# Inputs.net
KiCad netlist of a schematic drawn in EAGLE
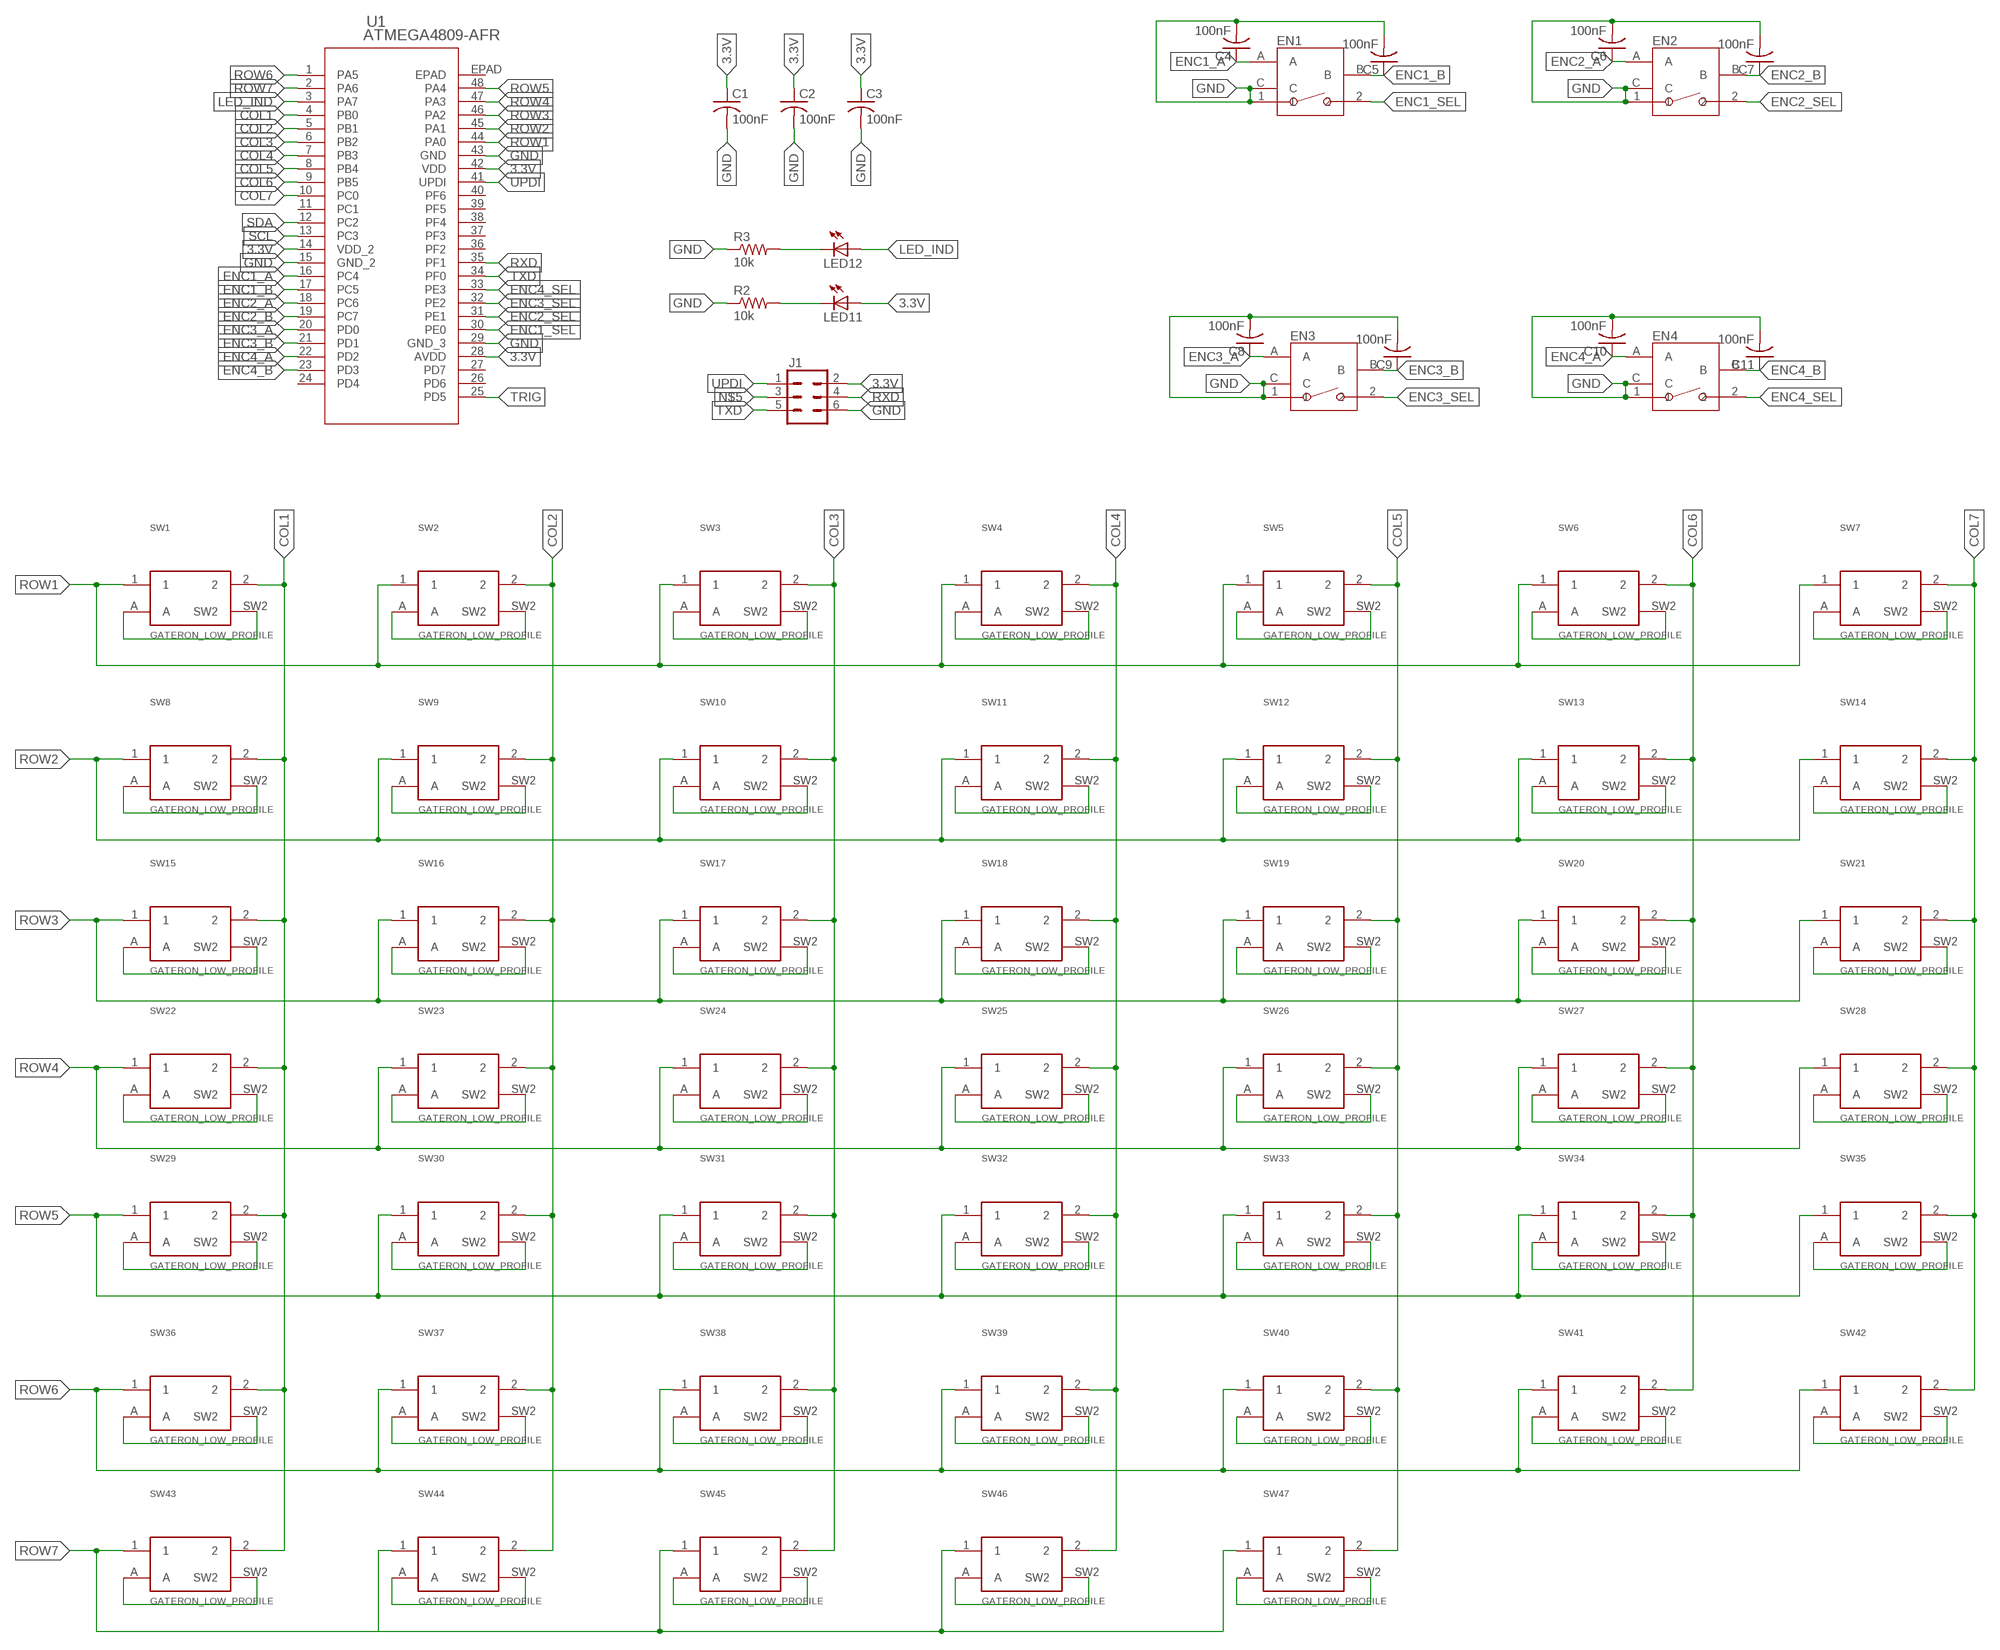
[diagram p0: schematic, sheet 1]

(export (version "E")
  (design (tool "Eeschema 10.0.6"))
  (components
    (comp (ref "C1")
      (value "100nF")
      (footprint "eagle-import:C0805")
      (libsource (lib "eagle-import") (part "C-USC0805"))
    )
    (comp (ref "C2")
      (value "100nF")
      (footprint "eagle-import:C0805")
      (libsource (lib "eagle-import") (part "C-USC0805"))
    )
    (comp (ref "C3")
      (value "100nF")
      (footprint "eagle-import:C0805")
      (libsource (lib "eagle-import") (part "C-USC0805"))
    )
    (comp (ref "C4")
      (value "100nF")
      (footprint "eagle-import:C0805")
      (libsource (lib "eagle-import") (part "C-USC0805"))
    )
    (comp (ref "C5")
      (value "100nF")
      (footprint "eagle-import:C0805")
      (libsource (lib "eagle-import") (part "C-USC0805"))
    )
    (comp (ref "C6")
      (value "100nF")
      (footprint "eagle-import:C0805")
      (libsource (lib "eagle-import") (part "C-USC0805"))
    )
    (comp (ref "C7")
      (value "100nF")
      (footprint "eagle-import:C0805")
      (libsource (lib "eagle-import") (part "C-USC0805"))
    )
    (comp (ref "C8")
      (value "100nF")
      (footprint "eagle-import:C0805")
      (libsource (lib "eagle-import") (part "C-USC0805"))
    )
    (comp (ref "C9")
      (value "100nF")
      (footprint "eagle-import:C0805")
      (libsource (lib "eagle-import") (part "C-USC0805"))
    )
    (comp (ref "C10")
      (value "100nF")
      (footprint "eagle-import:C0805")
      (libsource (lib "eagle-import") (part "C-USC0805"))
    )
    (comp (ref "C11")
      (value "100nF")
      (footprint "eagle-import:C0805")
      (libsource (lib "eagle-import") (part "C-USC0805"))
    )
    (comp (ref "EN1")
      (value "PEC11R-4215K-S0024")
      (footprint "eagle-import:PEC11R-4215K-S0024")
      (fields
        (field (name "DIGIKEY_PARTNO") "PEC11R-4215K-S0024-ND")
        (field (name "MANUFACTURER") "Bourns Inc.")
        (field (name "SPICEPREFIX") "X")
        (field (name "CREATED_BY") "PCBLayout.com")
      )
      (libsource (lib "eagle-import") (part "PEC11R-4215K-S0024"))
    )
    (comp (ref "EN2")
      (value "PEC11R-4215K-S0024")
      (footprint "eagle-import:PEC11R-4215K-S0024")
      (fields
        (field (name "DIGIKEY_PARTNO") "PEC11R-4215K-S0024-ND")
        (field (name "MANUFACTURER") "Bourns Inc.")
        (field (name "SPICEPREFIX") "X")
        (field (name "CREATED_BY") "PCBLayout.com")
      )
      (libsource (lib "eagle-import") (part "PEC11R-4215K-S0024"))
    )
    (comp (ref "EN3")
      (value "PEC11R-4215K-S0024")
      (footprint "eagle-import:PEC11R-4215K-S0024")
      (fields
        (field (name "DIGIKEY_PARTNO") "PEC11R-4215K-S0024-ND")
        (field (name "MANUFACTURER") "Bourns Inc.")
        (field (name "SPICEPREFIX") "X")
        (field (name "CREATED_BY") "PCBLayout.com")
      )
      (libsource (lib "eagle-import") (part "PEC11R-4215K-S0024"))
    )
    (comp (ref "EN4")
      (value "PEC11R-4215K-S0024")
      (footprint "eagle-import:PEC11R-4215K-S0024")
      (fields
        (field (name "DIGIKEY_PARTNO") "PEC11R-4215K-S0024-ND")
        (field (name "MANUFACTURER") "Bourns Inc.")
        (field (name "SPICEPREFIX") "X")
        (field (name "CREATED_BY") "PCBLayout.com")
      )
      (libsource (lib "eagle-import") (part "PEC11R-4215K-S0024"))
    )
    (comp (ref "J1")
      (value "CONN_03X2FEMALE_SMD")
      (footprint "eagle-import:2X3_SMD")
      (libsource (lib "eagle-import") (part "CONN_03X2FEMALE_SMD"))
    )
    (comp (ref "LED11")
      (value "LEDCHIPLED_0805")
      (footprint "eagle-import:CHIPLED_0805")
      (libsource (lib "eagle-import") (part "LEDCHIPLED_0805"))
    )
    (comp (ref "LED12")
      (value "LEDCHIPLED_0805")
      (footprint "eagle-import:CHIPLED_0805")
      (libsource (lib "eagle-import") (part "LEDCHIPLED_0805"))
    )
    (comp (ref "R2")
      (value "10k")
      (footprint "eagle-import:R0805")
      (libsource (lib "eagle-import") (part "R-US_R0805"))
    )
    (comp (ref "R3")
      (value "10k")
      (footprint "eagle-import:R0805")
      (libsource (lib "eagle-import") (part "R-US_R0805"))
    )
    (comp (ref "SW1")
      (value "GATERON_LOW_PROFILE")
      (footprint "eagle-import:GATERON_LP_PLAIN")
      (libsource (lib "eagle-import") (part "GATERON_LOW_PROFILE"))
    )
    (comp (ref "SW2")
      (value "GATERON_LOW_PROFILE")
      (footprint "eagle-import:GATERON_LP_PLAIN")
      (libsource (lib "eagle-import") (part "GATERON_LOW_PROFILE"))
    )
    (comp (ref "SW3")
      (value "GATERON_LOW_PROFILE")
      (footprint "eagle-import:GATERON_LP_PLAIN")
      (libsource (lib "eagle-import") (part "GATERON_LOW_PROFILE"))
    )
    (comp (ref "SW4")
      (value "GATERON_LOW_PROFILE")
      (footprint "eagle-import:GATERON_LP_PLAIN")
      (libsource (lib "eagle-import") (part "GATERON_LOW_PROFILE"))
    )
    (comp (ref "SW5")
      (value "GATERON_LOW_PROFILE")
      (footprint "eagle-import:GATERON_LP_PLAIN")
      (libsource (lib "eagle-import") (part "GATERON_LOW_PROFILE"))
    )
    (comp (ref "SW6")
      (value "GATERON_LOW_PROFILE")
      (footprint "eagle-import:GATERON_LP_PLAIN")
      (libsource (lib "eagle-import") (part "GATERON_LOW_PROFILE"))
    )
    (comp (ref "SW7")
      (value "GATERON_LOW_PROFILE")
      (footprint "eagle-import:GATERON_LP_PLAIN")
      (libsource (lib "eagle-import") (part "GATERON_LOW_PROFILE"))
    )
    (comp (ref "SW8")
      (value "GATERON_LOW_PROFILE")
      (footprint "eagle-import:GATERON_LP_PLAIN")
      (libsource (lib "eagle-import") (part "GATERON_LOW_PROFILE"))
    )
    (comp (ref "SW9")
      (value "GATERON_LOW_PROFILE")
      (footprint "eagle-import:GATERON_LP_PLAIN")
      (libsource (lib "eagle-import") (part "GATERON_LOW_PROFILE"))
    )
    (comp (ref "SW10")
      (value "GATERON_LOW_PROFILE")
      (footprint "eagle-import:GATERON_LP_PLAIN")
      (libsource (lib "eagle-import") (part "GATERON_LOW_PROFILE"))
    )
    (comp (ref "SW11")
      (value "GATERON_LOW_PROFILE")
      (footprint "eagle-import:GATERON_LP_PLAIN")
      (libsource (lib "eagle-import") (part "GATERON_LOW_PROFILE"))
    )
    (comp (ref "SW12")
      (value "GATERON_LOW_PROFILE")
      (footprint "eagle-import:GATERON_LP_PLAIN")
      (libsource (lib "eagle-import") (part "GATERON_LOW_PROFILE"))
    )
    (comp (ref "SW13")
      (value "GATERON_LOW_PROFILE")
      (footprint "eagle-import:GATERON_LP_PLAIN")
      (libsource (lib "eagle-import") (part "GATERON_LOW_PROFILE"))
    )
    (comp (ref "SW14")
      (value "GATERON_LOW_PROFILE")
      (footprint "eagle-import:GATERON_LP_PLAIN")
      (libsource (lib "eagle-import") (part "GATERON_LOW_PROFILE"))
    )
    (comp (ref "SW15")
      (value "GATERON_LOW_PROFILE")
      (footprint "eagle-import:GATERON_LP_PLAIN")
      (libsource (lib "eagle-import") (part "GATERON_LOW_PROFILE"))
    )
    (comp (ref "SW16")
      (value "GATERON_LOW_PROFILE")
      (footprint "eagle-import:GATERON_LP_PLAIN")
      (libsource (lib "eagle-import") (part "GATERON_LOW_PROFILE"))
    )
    (comp (ref "SW17")
      (value "GATERON_LOW_PROFILE")
      (footprint "eagle-import:GATERON_LP_PLAIN")
      (libsource (lib "eagle-import") (part "GATERON_LOW_PROFILE"))
    )
    (comp (ref "SW18")
      (value "GATERON_LOW_PROFILE")
      (footprint "eagle-import:GATERON_LP_PLAIN")
      (libsource (lib "eagle-import") (part "GATERON_LOW_PROFILE"))
    )
    (comp (ref "SW19")
      (value "GATERON_LOW_PROFILE")
      (footprint "eagle-import:GATERON_LP_PLAIN")
      (libsource (lib "eagle-import") (part "GATERON_LOW_PROFILE"))
    )
    (comp (ref "SW20")
      (value "GATERON_LOW_PROFILE")
      (footprint "eagle-import:GATERON_LP_PLAIN")
      (libsource (lib "eagle-import") (part "GATERON_LOW_PROFILE"))
    )
    (comp (ref "SW21")
      (value "GATERON_LOW_PROFILE")
      (footprint "eagle-import:GATERON_LP_PLAIN")
      (libsource (lib "eagle-import") (part "GATERON_LOW_PROFILE"))
    )
    (comp (ref "SW22")
      (value "GATERON_LOW_PROFILE")
      (footprint "eagle-import:GATERON_LP_PLAIN")
      (libsource (lib "eagle-import") (part "GATERON_LOW_PROFILE"))
    )
    (comp (ref "SW23")
      (value "GATERON_LOW_PROFILE")
      (footprint "eagle-import:GATERON_LP_PLAIN")
      (libsource (lib "eagle-import") (part "GATERON_LOW_PROFILE"))
    )
    (comp (ref "SW24")
      (value "GATERON_LOW_PROFILE")
      (footprint "eagle-import:GATERON_LP_PLAIN")
      (libsource (lib "eagle-import") (part "GATERON_LOW_PROFILE"))
    )
    (comp (ref "SW25")
      (value "GATERON_LOW_PROFILE")
      (footprint "eagle-import:GATERON_LP_PLAIN")
      (libsource (lib "eagle-import") (part "GATERON_LOW_PROFILE"))
    )
    (comp (ref "SW26")
      (value "GATERON_LOW_PROFILE")
      (footprint "eagle-import:GATERON_LP_PLAIN")
      (libsource (lib "eagle-import") (part "GATERON_LOW_PROFILE"))
    )
    (comp (ref "SW27")
      (value "GATERON_LOW_PROFILE")
      (footprint "eagle-import:GATERON_LP_PLAIN")
      (libsource (lib "eagle-import") (part "GATERON_LOW_PROFILE"))
    )
    (comp (ref "SW28")
      (value "GATERON_LOW_PROFILE")
      (footprint "eagle-import:GATERON_LP_PLAIN")
      (libsource (lib "eagle-import") (part "GATERON_LOW_PROFILE"))
    )
    (comp (ref "SW29")
      (value "GATERON_LOW_PROFILE")
      (footprint "eagle-import:GATERON_LP_PLAIN")
      (libsource (lib "eagle-import") (part "GATERON_LOW_PROFILE"))
    )
    (comp (ref "SW30")
      (value "GATERON_LOW_PROFILE")
      (footprint "eagle-import:GATERON_LP_PLAIN")
      (libsource (lib "eagle-import") (part "GATERON_LOW_PROFILE"))
    )
    (comp (ref "SW31")
      (value "GATERON_LOW_PROFILE")
      (footprint "eagle-import:GATERON_LP_PLAIN")
      (libsource (lib "eagle-import") (part "GATERON_LOW_PROFILE"))
    )
    (comp (ref "SW32")
      (value "GATERON_LOW_PROFILE")
      (footprint "eagle-import:GATERON_LP_PLAIN")
      (libsource (lib "eagle-import") (part "GATERON_LOW_PROFILE"))
    )
    (comp (ref "SW33")
      (value "GATERON_LOW_PROFILE")
      (footprint "eagle-import:GATERON_LP_PLAIN")
      (libsource (lib "eagle-import") (part "GATERON_LOW_PROFILE"))
    )
    (comp (ref "SW34")
      (value "GATERON_LOW_PROFILE")
      (footprint "eagle-import:GATERON_LP_PLAIN")
      (libsource (lib "eagle-import") (part "GATERON_LOW_PROFILE"))
    )
    (comp (ref "SW35")
      (value "GATERON_LOW_PROFILE")
      (footprint "eagle-import:GATERON_LP_PLAIN")
      (libsource (lib "eagle-import") (part "GATERON_LOW_PROFILE"))
    )
    (comp (ref "SW36")
      (value "GATERON_LOW_PROFILE")
      (footprint "eagle-import:GATERON_LP_PLAIN")
      (libsource (lib "eagle-import") (part "GATERON_LOW_PROFILE"))
    )
    (comp (ref "SW37")
      (value "GATERON_LOW_PROFILE")
      (footprint "eagle-import:GATERON_LP_PLAIN")
      (libsource (lib "eagle-import") (part "GATERON_LOW_PROFILE"))
    )
    (comp (ref "SW38")
      (value "GATERON_LOW_PROFILE")
      (footprint "eagle-import:GATERON_LP_PLAIN")
      (libsource (lib "eagle-import") (part "GATERON_LOW_PROFILE"))
    )
    (comp (ref "SW39")
      (value "GATERON_LOW_PROFILE")
      (footprint "eagle-import:GATERON_LP_PLAIN")
      (libsource (lib "eagle-import") (part "GATERON_LOW_PROFILE"))
    )
    (comp (ref "SW40")
      (value "GATERON_LOW_PROFILE")
      (footprint "eagle-import:GATERON_LP_PLAIN")
      (libsource (lib "eagle-import") (part "GATERON_LOW_PROFILE"))
    )
    (comp (ref "SW41")
      (value "GATERON_LOW_PROFILE")
      (footprint "eagle-import:GATERON_LP_PLAIN")
      (libsource (lib "eagle-import") (part "GATERON_LOW_PROFILE"))
    )
    (comp (ref "SW42")
      (value "GATERON_LOW_PROFILE")
      (footprint "eagle-import:GATERON_LP_PLAIN")
      (libsource (lib "eagle-import") (part "GATERON_LOW_PROFILE"))
    )
    (comp (ref "SW43")
      (value "GATERON_LOW_PROFILE")
      (footprint "eagle-import:GATERON_LP_PLAIN")
      (libsource (lib "eagle-import") (part "GATERON_LOW_PROFILE"))
    )
    (comp (ref "SW44")
      (value "GATERON_LOW_PROFILE")
      (footprint "eagle-import:GATERON_LP_PLAIN")
      (libsource (lib "eagle-import") (part "GATERON_LOW_PROFILE"))
    )
    (comp (ref "SW45")
      (value "GATERON_LOW_PROFILE")
      (footprint "eagle-import:GATERON_LP_PLAIN")
      (libsource (lib "eagle-import") (part "GATERON_LOW_PROFILE"))
    )
    (comp (ref "SW46")
      (value "GATERON_LOW_PROFILE")
      (footprint "eagle-import:GATERON_LP_PLAIN")
      (libsource (lib "eagle-import") (part "GATERON_LOW_PROFILE"))
    )
    (comp (ref "SW47")
      (value "GATERON_LOW_PROFILE")
      (footprint "eagle-import:GATERON_LP_PLAIN")
      (libsource (lib "eagle-import") (part "GATERON_LOW_PROFILE"))
    )
    (comp (ref "U1")
      (value "ATMEGA4809-AFR")
      (footprint "eagle-import:TQFP48_7X7MC_MCH")
      (fields (field (name "COPYRIGHT") "Copyright (C) 2018 Accelerated Designs. All rights reserved"))
      (libsource (lib "eagle-import") (part "ATMEGA4809-AFR"))
    )
  )
  (nets
    (net (code "1") (name "3.3V") (class "Default")
      (node (ref "C1") (pin "1") (pinfunction "1_1") (pintype "passive"))
      (node (ref "C2") (pin "1") (pinfunction "1_1") (pintype "passive"))
      (node (ref "C3") (pin "1") (pinfunction "1_1") (pintype "passive"))
      (node (ref "J1") (pin "2") (pinfunction "2_2") (pintype "bidirectional"))
      (node (ref "LED11") (pin "A") (pinfunction "A_A") (pintype "passive"))
      (node (ref "U1") (pin "14") (pinfunction "VDD_2_14") (pintype "power_in"))
      (node (ref "U1") (pin "28") (pinfunction "AVDD_28") (pintype "power_in"))
      (node (ref "U1") (pin "42") (pinfunction "VDD_42") (pintype "power_in"))
    )
    (net (code "2") (name "COL1") (class "Default")
      (node (ref "SW1") (pin "2") (pinfunction "2_2") (pintype "bidirectional"))
      (node (ref "SW15") (pin "2") (pinfunction "2_2") (pintype "bidirectional"))
      (node (ref "SW22") (pin "2") (pinfunction "2_2") (pintype "bidirectional"))
      (node (ref "SW29") (pin "2") (pinfunction "2_2") (pintype "bidirectional"))
      (node (ref "SW36") (pin "2") (pinfunction "2_2") (pintype "bidirectional"))
      (node (ref "SW43") (pin "2") (pinfunction "2_2") (pintype "bidirectional"))
      (node (ref "SW8") (pin "2") (pinfunction "2_2") (pintype "bidirectional"))
      (node (ref "U1") (pin "4") (pinfunction "PB0_4") (pintype "bidirectional"))
    )
    (net (code "3") (name "COL2") (class "Default")
      (node (ref "SW16") (pin "2") (pinfunction "2_2") (pintype "bidirectional"))
      (node (ref "SW2") (pin "2") (pinfunction "2_2") (pintype "bidirectional"))
      (node (ref "SW23") (pin "2") (pinfunction "2_2") (pintype "bidirectional"))
      (node (ref "SW30") (pin "2") (pinfunction "2_2") (pintype "bidirectional"))
      (node (ref "SW37") (pin "2") (pinfunction "2_2") (pintype "bidirectional"))
      (node (ref "SW44") (pin "2") (pinfunction "2_2") (pintype "bidirectional"))
      (node (ref "SW9") (pin "2") (pinfunction "2_2") (pintype "bidirectional"))
      (node (ref "U1") (pin "5") (pinfunction "PB1_5") (pintype "bidirectional"))
    )
    (net (code "4") (name "COL3") (class "Default")
      (node (ref "SW10") (pin "2") (pinfunction "2_2") (pintype "bidirectional"))
      (node (ref "SW17") (pin "2") (pinfunction "2_2") (pintype "bidirectional"))
      (node (ref "SW24") (pin "2") (pinfunction "2_2") (pintype "bidirectional"))
      (node (ref "SW3") (pin "2") (pinfunction "2_2") (pintype "bidirectional"))
      (node (ref "SW31") (pin "2") (pinfunction "2_2") (pintype "bidirectional"))
      (node (ref "SW38") (pin "2") (pinfunction "2_2") (pintype "bidirectional"))
      (node (ref "SW45") (pin "2") (pinfunction "2_2") (pintype "bidirectional"))
      (node (ref "U1") (pin "6") (pinfunction "PB2_6") (pintype "bidirectional"))
    )
    (net (code "5") (name "COL4") (class "Default")
      (node (ref "SW11") (pin "2") (pinfunction "2_2") (pintype "bidirectional"))
      (node (ref "SW18") (pin "2") (pinfunction "2_2") (pintype "bidirectional"))
      (node (ref "SW25") (pin "2") (pinfunction "2_2") (pintype "bidirectional"))
      (node (ref "SW32") (pin "2") (pinfunction "2_2") (pintype "bidirectional"))
      (node (ref "SW39") (pin "2") (pinfunction "2_2") (pintype "bidirectional"))
      (node (ref "SW4") (pin "2") (pinfunction "2_2") (pintype "bidirectional"))
      (node (ref "SW46") (pin "2") (pinfunction "2_2") (pintype "bidirectional"))
      (node (ref "U1") (pin "7") (pinfunction "PB3_7") (pintype "bidirectional"))
    )
    (net (code "6") (name "COL5") (class "Default")
      (node (ref "SW12") (pin "2") (pinfunction "2_2") (pintype "bidirectional"))
      (node (ref "SW19") (pin "2") (pinfunction "2_2") (pintype "bidirectional"))
      (node (ref "SW26") (pin "2") (pinfunction "2_2") (pintype "bidirectional"))
      (node (ref "SW33") (pin "2") (pinfunction "2_2") (pintype "bidirectional"))
      (node (ref "SW40") (pin "2") (pinfunction "2_2") (pintype "bidirectional"))
      (node (ref "SW47") (pin "2") (pinfunction "2_2") (pintype "bidirectional"))
      (node (ref "SW5") (pin "2") (pinfunction "2_2") (pintype "bidirectional"))
      (node (ref "U1") (pin "8") (pinfunction "PB4_8") (pintype "bidirectional"))
    )
    (net (code "7") (name "COL6") (class "Default")
      (node (ref "SW13") (pin "2") (pinfunction "2_2") (pintype "bidirectional"))
      (node (ref "SW20") (pin "2") (pinfunction "2_2") (pintype "bidirectional"))
      (node (ref "SW27") (pin "2") (pinfunction "2_2") (pintype "bidirectional"))
      (node (ref "SW34") (pin "2") (pinfunction "2_2") (pintype "bidirectional"))
      (node (ref "SW41") (pin "2") (pinfunction "2_2") (pintype "bidirectional"))
      (node (ref "SW6") (pin "2") (pinfunction "2_2") (pintype "bidirectional"))
      (node (ref "U1") (pin "9") (pinfunction "PB5_9") (pintype "bidirectional"))
    )
    (net (code "8") (name "COL7") (class "Default")
      (node (ref "SW14") (pin "2") (pinfunction "2_2") (pintype "bidirectional"))
      (node (ref "SW21") (pin "2") (pinfunction "2_2") (pintype "bidirectional"))
      (node (ref "SW28") (pin "2") (pinfunction "2_2") (pintype "bidirectional"))
      (node (ref "SW35") (pin "2") (pinfunction "2_2") (pintype "bidirectional"))
      (node (ref "SW42") (pin "2") (pinfunction "2_2") (pintype "bidirectional"))
      (node (ref "SW7") (pin "2") (pinfunction "2_2") (pintype "bidirectional"))
      (node (ref "U1") (pin "10") (pinfunction "PC0_10") (pintype "bidirectional"))
    )
    (net (code "9") (name "ENC1_A") (class "Default")
      (node (ref "C4") (pin "1") (pinfunction "1_1") (pintype "passive"))
      (node (ref "EN1") (pin "A") (pinfunction "A_A") (pintype "passive"))
      (node (ref "U1") (pin "16") (pinfunction "PC4_16") (pintype "bidirectional"))
    )
    (net (code "10") (name "ENC1_B") (class "Default")
      (node (ref "C5") (pin "1") (pinfunction "1_1") (pintype "passive"))
      (node (ref "EN1") (pin "B") (pinfunction "B_B") (pintype "passive"))
      (node (ref "U1") (pin "17") (pinfunction "PC5_17") (pintype "bidirectional"))
    )
    (net (code "11") (name "ENC1_SEL") (class "Default")
      (node (ref "EN1") (pin "2") (pinfunction "2_2") (pintype "passive"))
      (node (ref "U1") (pin "30") (pinfunction "PE0_30") (pintype "bidirectional"))
    )
    (net (code "12") (name "ENC2_A") (class "Default")
      (node (ref "C6") (pin "1") (pinfunction "1_1") (pintype "passive"))
      (node (ref "EN2") (pin "A") (pinfunction "A_A") (pintype "passive"))
      (node (ref "U1") (pin "18") (pinfunction "PC6_18") (pintype "bidirectional"))
    )
    (net (code "13") (name "ENC2_B") (class "Default")
      (node (ref "C7") (pin "1") (pinfunction "1_1") (pintype "passive"))
      (node (ref "EN2") (pin "B") (pinfunction "B_B") (pintype "passive"))
      (node (ref "U1") (pin "19") (pinfunction "PC7_19") (pintype "bidirectional"))
    )
    (net (code "14") (name "ENC2_SEL") (class "Default")
      (node (ref "EN2") (pin "2") (pinfunction "2_2") (pintype "passive"))
      (node (ref "U1") (pin "31") (pinfunction "PE1_31") (pintype "bidirectional"))
    )
    (net (code "15") (name "ENC3_A") (class "Default")
      (node (ref "C8") (pin "1") (pinfunction "1_1") (pintype "passive"))
      (node (ref "EN3") (pin "A") (pinfunction "A_A") (pintype "passive"))
      (node (ref "U1") (pin "20") (pinfunction "PD0_20") (pintype "bidirectional"))
    )
    (net (code "16") (name "ENC3_B") (class "Default")
      (node (ref "C9") (pin "1") (pinfunction "1_1") (pintype "passive"))
      (node (ref "EN3") (pin "B") (pinfunction "B_B") (pintype "passive"))
      (node (ref "U1") (pin "21") (pinfunction "PD1_21") (pintype "bidirectional"))
    )
    (net (code "17") (name "ENC3_SEL") (class "Default")
      (node (ref "EN3") (pin "2") (pinfunction "2_2") (pintype "passive"))
      (node (ref "U1") (pin "32") (pinfunction "PE2_32") (pintype "bidirectional"))
    )
    (net (code "18") (name "ENC4_A") (class "Default")
      (node (ref "C10") (pin "1") (pinfunction "1_1") (pintype "passive"))
      (node (ref "EN4") (pin "A") (pinfunction "A_A") (pintype "passive"))
      (node (ref "U1") (pin "22") (pinfunction "PD2_22") (pintype "bidirectional"))
    )
    (net (code "19") (name "ENC4_B") (class "Default")
      (node (ref "C11") (pin "1") (pinfunction "1_1") (pintype "passive"))
      (node (ref "EN4") (pin "B") (pinfunction "B_B") (pintype "passive"))
      (node (ref "U1") (pin "23") (pinfunction "PD3_23") (pintype "bidirectional"))
    )
    (net (code "20") (name "ENC4_SEL") (class "Default")
      (node (ref "EN4") (pin "2") (pinfunction "2_2") (pintype "passive"))
      (node (ref "U1") (pin "33") (pinfunction "PE3_33") (pintype "bidirectional"))
    )
    (net (code "21") (name "GND") (class "Default")
      (node (ref "C1") (pin "2") (pinfunction "2_2") (pintype "passive"))
      (node (ref "C10") (pin "2") (pinfunction "2_2") (pintype "passive"))
      (node (ref "C11") (pin "2") (pinfunction "2_2") (pintype "passive"))
      (node (ref "C2") (pin "2") (pinfunction "2_2") (pintype "passive"))
      (node (ref "C3") (pin "2") (pinfunction "2_2") (pintype "passive"))
      (node (ref "C4") (pin "2") (pinfunction "2_2") (pintype "passive"))
      (node (ref "C5") (pin "2") (pinfunction "2_2") (pintype "passive"))
      (node (ref "C6") (pin "2") (pinfunction "2_2") (pintype "passive"))
      (node (ref "C7") (pin "2") (pinfunction "2_2") (pintype "passive"))
      (node (ref "C8") (pin "2") (pinfunction "2_2") (pintype "passive"))
      (node (ref "C9") (pin "2") (pinfunction "2_2") (pintype "passive"))
      (node (ref "EN1") (pin "1") (pinfunction "1_1") (pintype "passive"))
      (node (ref "EN1") (pin "C") (pinfunction "C_C") (pintype "passive"))
      (node (ref "EN2") (pin "1") (pinfunction "1_1") (pintype "passive"))
      (node (ref "EN2") (pin "C") (pinfunction "C_C") (pintype "passive"))
      (node (ref "EN3") (pin "1") (pinfunction "1_1") (pintype "passive"))
      (node (ref "EN3") (pin "C") (pinfunction "C_C") (pintype "passive"))
      (node (ref "EN4") (pin "1") (pinfunction "1_1") (pintype "passive"))
      (node (ref "EN4") (pin "C") (pinfunction "C_C") (pintype "passive"))
      (node (ref "J1") (pin "6") (pinfunction "6_6") (pintype "bidirectional"))
      (node (ref "R2") (pin "1") (pinfunction "1_1") (pintype "passive"))
      (node (ref "R3") (pin "1") (pinfunction "1_1") (pintype "passive"))
      (node (ref "U1") (pin "15") (pinfunction "GND_2_15") (pintype "power_in"))
      (node (ref "U1") (pin "29") (pinfunction "GND_3_29") (pintype "power_in"))
      (node (ref "U1") (pin "43") (pinfunction "GND_43") (pintype "power_in"))
    )
    (net (code "22") (name "LED_IND") (class "Default")
      (node (ref "LED12") (pin "A") (pinfunction "A_A") (pintype "passive"))
      (node (ref "U1") (pin "3") (pinfunction "PA7_3") (pintype "bidirectional"))
    )
    (net (code "23") (name "N$5") (class "Default")
      (node (ref "J1") (pin "3") (pinfunction "3_3") (pintype "bidirectional"))
    )
    (net (code "24") (name "Net-(LED11-PadC)") (class "Default")
      (node (ref "LED11") (pin "C") (pinfunction "C_C") (pintype "passive"))
      (node (ref "R2") (pin "2") (pinfunction "2_2") (pintype "passive"))
    )
    (net (code "25") (name "Net-(LED12-PadC)") (class "Default")
      (node (ref "LED12") (pin "C") (pinfunction "C_C") (pintype "passive"))
      (node (ref "R3") (pin "2") (pinfunction "2_2") (pintype "passive"))
    )
    (net (code "26") (name "Net-(SW1-PadA)") (class "Default")
      (node (ref "SW1") (pin "A") (pinfunction "A_A") (pintype "bidirectional"))
      (node (ref "SW1") (pin "SW2") (pinfunction "SW2_SW2") (pintype "bidirectional"))
    )
    (net (code "27") (name "Net-(SW2-PadA)") (class "Default")
      (node (ref "SW2") (pin "A") (pinfunction "A_A") (pintype "bidirectional"))
      (node (ref "SW2") (pin "SW2") (pinfunction "SW2_SW2") (pintype "bidirectional"))
    )
    (net (code "28") (name "Net-(SW3-PadA)") (class "Default")
      (node (ref "SW3") (pin "A") (pinfunction "A_A") (pintype "bidirectional"))
      (node (ref "SW3") (pin "SW2") (pinfunction "SW2_SW2") (pintype "bidirectional"))
    )
    (net (code "29") (name "Net-(SW4-PadA)") (class "Default")
      (node (ref "SW4") (pin "A") (pinfunction "A_A") (pintype "bidirectional"))
      (node (ref "SW4") (pin "SW2") (pinfunction "SW2_SW2") (pintype "bidirectional"))
    )
    (net (code "30") (name "Net-(SW5-PadA)") (class "Default")
      (node (ref "SW5") (pin "A") (pinfunction "A_A") (pintype "bidirectional"))
      (node (ref "SW5") (pin "SW2") (pinfunction "SW2_SW2") (pintype "bidirectional"))
    )
    (net (code "31") (name "Net-(SW6-PadA)") (class "Default")
      (node (ref "SW6") (pin "A") (pinfunction "A_A") (pintype "bidirectional"))
      (node (ref "SW6") (pin "SW2") (pinfunction "SW2_SW2") (pintype "bidirectional"))
    )
    (net (code "32") (name "Net-(SW7-PadA)") (class "Default")
      (node (ref "SW7") (pin "A") (pinfunction "A_A") (pintype "bidirectional"))
      (node (ref "SW7") (pin "SW2") (pinfunction "SW2_SW2") (pintype "bidirectional"))
    )
    (net (code "33") (name "Net-(SW8-PadA)") (class "Default")
      (node (ref "SW8") (pin "A") (pinfunction "A_A") (pintype "bidirectional"))
      (node (ref "SW8") (pin "SW2") (pinfunction "SW2_SW2") (pintype "bidirectional"))
    )
    (net (code "34") (name "Net-(SW9-PadA)") (class "Default")
      (node (ref "SW9") (pin "A") (pinfunction "A_A") (pintype "bidirectional"))
      (node (ref "SW9") (pin "SW2") (pinfunction "SW2_SW2") (pintype "bidirectional"))
    )
    (net (code "35") (name "Net-(SW10-PadA)") (class "Default")
      (node (ref "SW10") (pin "A") (pinfunction "A_A") (pintype "bidirectional"))
      (node (ref "SW10") (pin "SW2") (pinfunction "SW2_SW2") (pintype "bidirectional"))
    )
    (net (code "36") (name "Net-(SW11-PadA)") (class "Default")
      (node (ref "SW11") (pin "A") (pinfunction "A_A") (pintype "bidirectional"))
      (node (ref "SW11") (pin "SW2") (pinfunction "SW2_SW2") (pintype "bidirectional"))
    )
    (net (code "37") (name "Net-(SW12-PadA)") (class "Default")
      (node (ref "SW12") (pin "A") (pinfunction "A_A") (pintype "bidirectional"))
      (node (ref "SW12") (pin "SW2") (pinfunction "SW2_SW2") (pintype "bidirectional"))
    )
    (net (code "38") (name "Net-(SW13-PadA)") (class "Default")
      (node (ref "SW13") (pin "A") (pinfunction "A_A") (pintype "bidirectional"))
      (node (ref "SW13") (pin "SW2") (pinfunction "SW2_SW2") (pintype "bidirectional"))
    )
    (net (code "39") (name "Net-(SW14-PadA)") (class "Default")
      (node (ref "SW14") (pin "A") (pinfunction "A_A") (pintype "bidirectional"))
      (node (ref "SW14") (pin "SW2") (pinfunction "SW2_SW2") (pintype "bidirectional"))
    )
    (net (code "40") (name "Net-(SW15-PadA)") (class "Default")
      (node (ref "SW15") (pin "A") (pinfunction "A_A") (pintype "bidirectional"))
      (node (ref "SW15") (pin "SW2") (pinfunction "SW2_SW2") (pintype "bidirectional"))
    )
    (net (code "41") (name "Net-(SW16-PadA)") (class "Default")
      (node (ref "SW16") (pin "A") (pinfunction "A_A") (pintype "bidirectional"))
      (node (ref "SW16") (pin "SW2") (pinfunction "SW2_SW2") (pintype "bidirectional"))
    )
    (net (code "42") (name "Net-(SW17-PadA)") (class "Default")
      (node (ref "SW17") (pin "A") (pinfunction "A_A") (pintype "bidirectional"))
      (node (ref "SW17") (pin "SW2") (pinfunction "SW2_SW2") (pintype "bidirectional"))
    )
    (net (code "43") (name "Net-(SW18-PadA)") (class "Default")
      (node (ref "SW18") (pin "A") (pinfunction "A_A") (pintype "bidirectional"))
      (node (ref "SW18") (pin "SW2") (pinfunction "SW2_SW2") (pintype "bidirectional"))
    )
    (net (code "44") (name "Net-(SW19-PadA)") (class "Default")
      (node (ref "SW19") (pin "A") (pinfunction "A_A") (pintype "bidirectional"))
      (node (ref "SW19") (pin "SW2") (pinfunction "SW2_SW2") (pintype "bidirectional"))
    )
    (net (code "45") (name "Net-(SW20-PadA)") (class "Default")
      (node (ref "SW20") (pin "A") (pinfunction "A_A") (pintype "bidirectional"))
      (node (ref "SW20") (pin "SW2") (pinfunction "SW2_SW2") (pintype "bidirectional"))
    )
    (net (code "46") (name "Net-(SW21-PadA)") (class "Default")
      (node (ref "SW21") (pin "A") (pinfunction "A_A") (pintype "bidirectional"))
      (node (ref "SW21") (pin "SW2") (pinfunction "SW2_SW2") (pintype "bidirectional"))
    )
    (net (code "47") (name "Net-(SW22-PadA)") (class "Default")
      (node (ref "SW22") (pin "A") (pinfunction "A_A") (pintype "bidirectional"))
      (node (ref "SW22") (pin "SW2") (pinfunction "SW2_SW2") (pintype "bidirectional"))
    )
    (net (code "48") (name "Net-(SW23-PadA)") (class "Default")
      (node (ref "SW23") (pin "A") (pinfunction "A_A") (pintype "bidirectional"))
      (node (ref "SW23") (pin "SW2") (pinfunction "SW2_SW2") (pintype "bidirectional"))
    )
    (net (code "49") (name "Net-(SW24-PadA)") (class "Default")
      (node (ref "SW24") (pin "A") (pinfunction "A_A") (pintype "bidirectional"))
      (node (ref "SW24") (pin "SW2") (pinfunction "SW2_SW2") (pintype "bidirectional"))
    )
    (net (code "50") (name "Net-(SW25-PadA)") (class "Default")
      (node (ref "SW25") (pin "A") (pinfunction "A_A") (pintype "bidirectional"))
      (node (ref "SW25") (pin "SW2") (pinfunction "SW2_SW2") (pintype "bidirectional"))
    )
    (net (code "51") (name "Net-(SW26-PadA)") (class "Default")
      (node (ref "SW26") (pin "A") (pinfunction "A_A") (pintype "bidirectional"))
      (node (ref "SW26") (pin "SW2") (pinfunction "SW2_SW2") (pintype "bidirectional"))
    )
    (net (code "52") (name "Net-(SW27-PadA)") (class "Default")
      (node (ref "SW27") (pin "A") (pinfunction "A_A") (pintype "bidirectional"))
      (node (ref "SW27") (pin "SW2") (pinfunction "SW2_SW2") (pintype "bidirectional"))
    )
    (net (code "53") (name "Net-(SW28-PadA)") (class "Default")
      (node (ref "SW28") (pin "A") (pinfunction "A_A") (pintype "bidirectional"))
      (node (ref "SW28") (pin "SW2") (pinfunction "SW2_SW2") (pintype "bidirectional"))
    )
    (net (code "54") (name "Net-(SW29-PadA)") (class "Default")
      (node (ref "SW29") (pin "A") (pinfunction "A_A") (pintype "bidirectional"))
      (node (ref "SW29") (pin "SW2") (pinfunction "SW2_SW2") (pintype "bidirectional"))
    )
    (net (code "55") (name "Net-(SW30-PadA)") (class "Default")
      (node (ref "SW30") (pin "A") (pinfunction "A_A") (pintype "bidirectional"))
      (node (ref "SW30") (pin "SW2") (pinfunction "SW2_SW2") (pintype "bidirectional"))
    )
    (net (code "56") (name "Net-(SW31-PadA)") (class "Default")
      (node (ref "SW31") (pin "A") (pinfunction "A_A") (pintype "bidirectional"))
      (node (ref "SW31") (pin "SW2") (pinfunction "SW2_SW2") (pintype "bidirectional"))
    )
    (net (code "57") (name "Net-(SW32-PadA)") (class "Default")
      (node (ref "SW32") (pin "A") (pinfunction "A_A") (pintype "bidirectional"))
      (node (ref "SW32") (pin "SW2") (pinfunction "SW2_SW2") (pintype "bidirectional"))
    )
    (net (code "58") (name "Net-(SW33-PadA)") (class "Default")
      (node (ref "SW33") (pin "A") (pinfunction "A_A") (pintype "bidirectional"))
      (node (ref "SW33") (pin "SW2") (pinfunction "SW2_SW2") (pintype "bidirectional"))
    )
    (net (code "59") (name "Net-(SW34-PadA)") (class "Default")
      (node (ref "SW34") (pin "A") (pinfunction "A_A") (pintype "bidirectional"))
      (node (ref "SW34") (pin "SW2") (pinfunction "SW2_SW2") (pintype "bidirectional"))
    )
    (net (code "60") (name "Net-(SW35-PadA)") (class "Default")
      (node (ref "SW35") (pin "A") (pinfunction "A_A") (pintype "bidirectional"))
      (node (ref "SW35") (pin "SW2") (pinfunction "SW2_SW2") (pintype "bidirectional"))
    )
    (net (code "61") (name "Net-(SW36-PadA)") (class "Default")
      (node (ref "SW36") (pin "A") (pinfunction "A_A") (pintype "bidirectional"))
      (node (ref "SW36") (pin "SW2") (pinfunction "SW2_SW2") (pintype "bidirectional"))
    )
    (net (code "62") (name "Net-(SW37-PadA)") (class "Default")
      (node (ref "SW37") (pin "A") (pinfunction "A_A") (pintype "bidirectional"))
      (node (ref "SW37") (pin "SW2") (pinfunction "SW2_SW2") (pintype "bidirectional"))
    )
    (net (code "63") (name "Net-(SW38-PadA)") (class "Default")
      (node (ref "SW38") (pin "A") (pinfunction "A_A") (pintype "bidirectional"))
      (node (ref "SW38") (pin "SW2") (pinfunction "SW2_SW2") (pintype "bidirectional"))
    )
    (net (code "64") (name "Net-(SW39-PadA)") (class "Default")
      (node (ref "SW39") (pin "A") (pinfunction "A_A") (pintype "bidirectional"))
      (node (ref "SW39") (pin "SW2") (pinfunction "SW2_SW2") (pintype "bidirectional"))
    )
    (net (code "65") (name "Net-(SW40-PadA)") (class "Default")
      (node (ref "SW40") (pin "A") (pinfunction "A_A") (pintype "bidirectional"))
      (node (ref "SW40") (pin "SW2") (pinfunction "SW2_SW2") (pintype "bidirectional"))
    )
    (net (code "66") (name "Net-(SW41-PadA)") (class "Default")
      (node (ref "SW41") (pin "A") (pinfunction "A_A") (pintype "bidirectional"))
      (node (ref "SW41") (pin "SW2") (pinfunction "SW2_SW2") (pintype "bidirectional"))
    )
    (net (code "67") (name "Net-(SW42-PadA)") (class "Default")
      (node (ref "SW42") (pin "A") (pinfunction "A_A") (pintype "bidirectional"))
      (node (ref "SW42") (pin "SW2") (pinfunction "SW2_SW2") (pintype "bidirectional"))
    )
    (net (code "68") (name "Net-(SW43-PadA)") (class "Default")
      (node (ref "SW43") (pin "A") (pinfunction "A_A") (pintype "bidirectional"))
      (node (ref "SW43") (pin "SW2") (pinfunction "SW2_SW2") (pintype "bidirectional"))
    )
    (net (code "69") (name "Net-(SW44-PadA)") (class "Default")
      (node (ref "SW44") (pin "A") (pinfunction "A_A") (pintype "bidirectional"))
      (node (ref "SW44") (pin "SW2") (pinfunction "SW2_SW2") (pintype "bidirectional"))
    )
    (net (code "70") (name "Net-(SW45-PadA)") (class "Default")
      (node (ref "SW45") (pin "A") (pinfunction "A_A") (pintype "bidirectional"))
      (node (ref "SW45") (pin "SW2") (pinfunction "SW2_SW2") (pintype "bidirectional"))
    )
    (net (code "71") (name "Net-(SW46-PadA)") (class "Default")
      (node (ref "SW46") (pin "A") (pinfunction "A_A") (pintype "bidirectional"))
      (node (ref "SW46") (pin "SW2") (pinfunction "SW2_SW2") (pintype "bidirectional"))
    )
    (net (code "72") (name "Net-(SW47-PadA)") (class "Default")
      (node (ref "SW47") (pin "A") (pinfunction "A_A") (pintype "bidirectional"))
      (node (ref "SW47") (pin "SW2") (pinfunction "SW2_SW2") (pintype "bidirectional"))
    )
    (net (code "73") (name "ROW1") (class "Default")
      (node (ref "SW1") (pin "1") (pinfunction "1_1") (pintype "bidirectional"))
      (node (ref "SW2") (pin "1") (pinfunction "1_1") (pintype "bidirectional"))
      (node (ref "SW3") (pin "1") (pinfunction "1_1") (pintype "bidirectional"))
      (node (ref "SW4") (pin "1") (pinfunction "1_1") (pintype "bidirectional"))
      (node (ref "SW5") (pin "1") (pinfunction "1_1") (pintype "bidirectional"))
      (node (ref "SW6") (pin "1") (pinfunction "1_1") (pintype "bidirectional"))
      (node (ref "SW7") (pin "1") (pinfunction "1_1") (pintype "bidirectional"))
      (node (ref "U1") (pin "44") (pinfunction "PA0_44") (pintype "bidirectional"))
    )
    (net (code "74") (name "ROW2") (class "Default")
      (node (ref "SW10") (pin "1") (pinfunction "1_1") (pintype "bidirectional"))
      (node (ref "SW11") (pin "1") (pinfunction "1_1") (pintype "bidirectional"))
      (node (ref "SW12") (pin "1") (pinfunction "1_1") (pintype "bidirectional"))
      (node (ref "SW13") (pin "1") (pinfunction "1_1") (pintype "bidirectional"))
      (node (ref "SW14") (pin "1") (pinfunction "1_1") (pintype "bidirectional"))
      (node (ref "SW8") (pin "1") (pinfunction "1_1") (pintype "bidirectional"))
      (node (ref "SW9") (pin "1") (pinfunction "1_1") (pintype "bidirectional"))
      (node (ref "U1") (pin "45") (pinfunction "PA1_45") (pintype "bidirectional"))
    )
    (net (code "75") (name "ROW3") (class "Default")
      (node (ref "SW15") (pin "1") (pinfunction "1_1") (pintype "bidirectional"))
      (node (ref "SW16") (pin "1") (pinfunction "1_1") (pintype "bidirectional"))
      (node (ref "SW17") (pin "1") (pinfunction "1_1") (pintype "bidirectional"))
      (node (ref "SW18") (pin "1") (pinfunction "1_1") (pintype "bidirectional"))
      (node (ref "SW19") (pin "1") (pinfunction "1_1") (pintype "bidirectional"))
      (node (ref "SW20") (pin "1") (pinfunction "1_1") (pintype "bidirectional"))
      (node (ref "SW21") (pin "1") (pinfunction "1_1") (pintype "bidirectional"))
      (node (ref "U1") (pin "46") (pinfunction "PA2_46") (pintype "bidirectional"))
    )
    (net (code "76") (name "ROW4") (class "Default")
      (node (ref "SW22") (pin "1") (pinfunction "1_1") (pintype "bidirectional"))
      (node (ref "SW23") (pin "1") (pinfunction "1_1") (pintype "bidirectional"))
      (node (ref "SW24") (pin "1") (pinfunction "1_1") (pintype "bidirectional"))
      (node (ref "SW25") (pin "1") (pinfunction "1_1") (pintype "bidirectional"))
      (node (ref "SW26") (pin "1") (pinfunction "1_1") (pintype "bidirectional"))
      (node (ref "SW27") (pin "1") (pinfunction "1_1") (pintype "bidirectional"))
      (node (ref "SW28") (pin "1") (pinfunction "1_1") (pintype "bidirectional"))
      (node (ref "U1") (pin "47") (pinfunction "PA3_47") (pintype "bidirectional"))
    )
    (net (code "77") (name "ROW5") (class "Default")
      (node (ref "SW29") (pin "1") (pinfunction "1_1") (pintype "bidirectional"))
      (node (ref "SW30") (pin "1") (pinfunction "1_1") (pintype "bidirectional"))
      (node (ref "SW31") (pin "1") (pinfunction "1_1") (pintype "bidirectional"))
      (node (ref "SW32") (pin "1") (pinfunction "1_1") (pintype "bidirectional"))
      (node (ref "SW33") (pin "1") (pinfunction "1_1") (pintype "bidirectional"))
      (node (ref "SW34") (pin "1") (pinfunction "1_1") (pintype "bidirectional"))
      (node (ref "SW35") (pin "1") (pinfunction "1_1") (pintype "bidirectional"))
      (node (ref "U1") (pin "48") (pinfunction "PA4_48") (pintype "bidirectional"))
    )
    (net (code "78") (name "ROW6") (class "Default")
      (node (ref "SW36") (pin "1") (pinfunction "1_1") (pintype "bidirectional"))
      (node (ref "SW37") (pin "1") (pinfunction "1_1") (pintype "bidirectional"))
      (node (ref "SW38") (pin "1") (pinfunction "1_1") (pintype "bidirectional"))
      (node (ref "SW39") (pin "1") (pinfunction "1_1") (pintype "bidirectional"))
      (node (ref "SW40") (pin "1") (pinfunction "1_1") (pintype "bidirectional"))
      (node (ref "SW41") (pin "1") (pinfunction "1_1") (pintype "bidirectional"))
      (node (ref "SW42") (pin "1") (pinfunction "1_1") (pintype "bidirectional"))
      (node (ref "U1") (pin "1") (pinfunction "PA5_1") (pintype "bidirectional"))
    )
    (net (code "79") (name "ROW7") (class "Default")
      (node (ref "SW43") (pin "1") (pinfunction "1_1") (pintype "bidirectional"))
      (node (ref "SW44") (pin "1") (pinfunction "1_1") (pintype "bidirectional"))
      (node (ref "SW45") (pin "1") (pinfunction "1_1") (pintype "bidirectional"))
      (node (ref "SW46") (pin "1") (pinfunction "1_1") (pintype "bidirectional"))
      (node (ref "SW47") (pin "1") (pinfunction "1_1") (pintype "bidirectional"))
      (node (ref "U1") (pin "2") (pinfunction "PA6_2") (pintype "bidirectional"))
    )
    (net (code "80") (name "RXD") (class "Default")
      (node (ref "J1") (pin "4") (pinfunction "4_4") (pintype "bidirectional"))
      (node (ref "U1") (pin "35") (pinfunction "PF1_35") (pintype "bidirectional"))
    )
    (net (code "81") (name "SCL") (class "Default")
      (node (ref "U1") (pin "13") (pinfunction "PC3_13") (pintype "bidirectional"))
    )
    (net (code "82") (name "SDA") (class "Default")
      (node (ref "U1") (pin "12") (pinfunction "PC2_12") (pintype "bidirectional"))
    )
    (net (code "83") (name "TRIG") (class "Default")
      (node (ref "U1") (pin "25") (pinfunction "PD5_25") (pintype "bidirectional"))
    )
    (net (code "84") (name "TXD") (class "Default")
      (node (ref "J1") (pin "5") (pinfunction "5_5") (pintype "bidirectional"))
      (node (ref "U1") (pin "34") (pinfunction "PF0_34") (pintype "bidirectional"))
    )
    (net (code "85") (name "UPDI") (class "Default")
      (node (ref "J1") (pin "1") (pinfunction "1_1") (pintype "bidirectional"))
      (node (ref "U1") (pin "41") (pinfunction "UPDI_41") (pintype "bidirectional"))
    )
    (net (code "86") (name "unconnected-(U1-PC1-Pad11)") (class "Default")
      (node (ref "U1") (pin "11") (pinfunction "PC1_11") (pintype "bidirectional"))
    )
    (net (code "87") (name "unconnected-(U1-PD4-Pad24)") (class "Default")
      (node (ref "U1") (pin "24") (pinfunction "PD4_24") (pintype "bidirectional"))
    )
    (net (code "88") (name "unconnected-(U1-PD6-Pad26)") (class "Default")
      (node (ref "U1") (pin "26") (pinfunction "PD6_26") (pintype "bidirectional"))
    )
    (net (code "89") (name "unconnected-(U1-PD7-Pad27)") (class "Default")
      (node (ref "U1") (pin "27") (pinfunction "PD7_27") (pintype "bidirectional"))
    )
    (net (code "90") (name "unconnected-(U1-PF2-Pad36)") (class "Default")
      (node (ref "U1") (pin "36") (pinfunction "PF2_36") (pintype "bidirectional"))
    )
    (net (code "91") (name "unconnected-(U1-PF3-Pad37)") (class "Default")
      (node (ref "U1") (pin "37") (pinfunction "PF3_37") (pintype "bidirectional"))
    )
    (net (code "92") (name "unconnected-(U1-PF4-Pad38)") (class "Default")
      (node (ref "U1") (pin "38") (pinfunction "PF4_38") (pintype "bidirectional"))
    )
    (net (code "93") (name "unconnected-(U1-PF5-Pad39)") (class "Default")
      (node (ref "U1") (pin "39") (pinfunction "PF5_39") (pintype "bidirectional"))
    )
    (net (code "94") (name "unconnected-(U1-PF6-Pad40)") (class "Default")
      (node (ref "U1") (pin "40") (pinfunction "PF6_40") (pintype "bidirectional"))
    )
    (net (code "95") (name "unconnected-(U1-PadEPAD)") (class "Default")
      (node (ref "U1") (pin "EPAD") (pinfunction "EPAD_EPAD") (pintype "passive"))
    )
  )
)
